# 2_RX_Control.net
KiCad netlist of a schematic drawn in Altium Designer
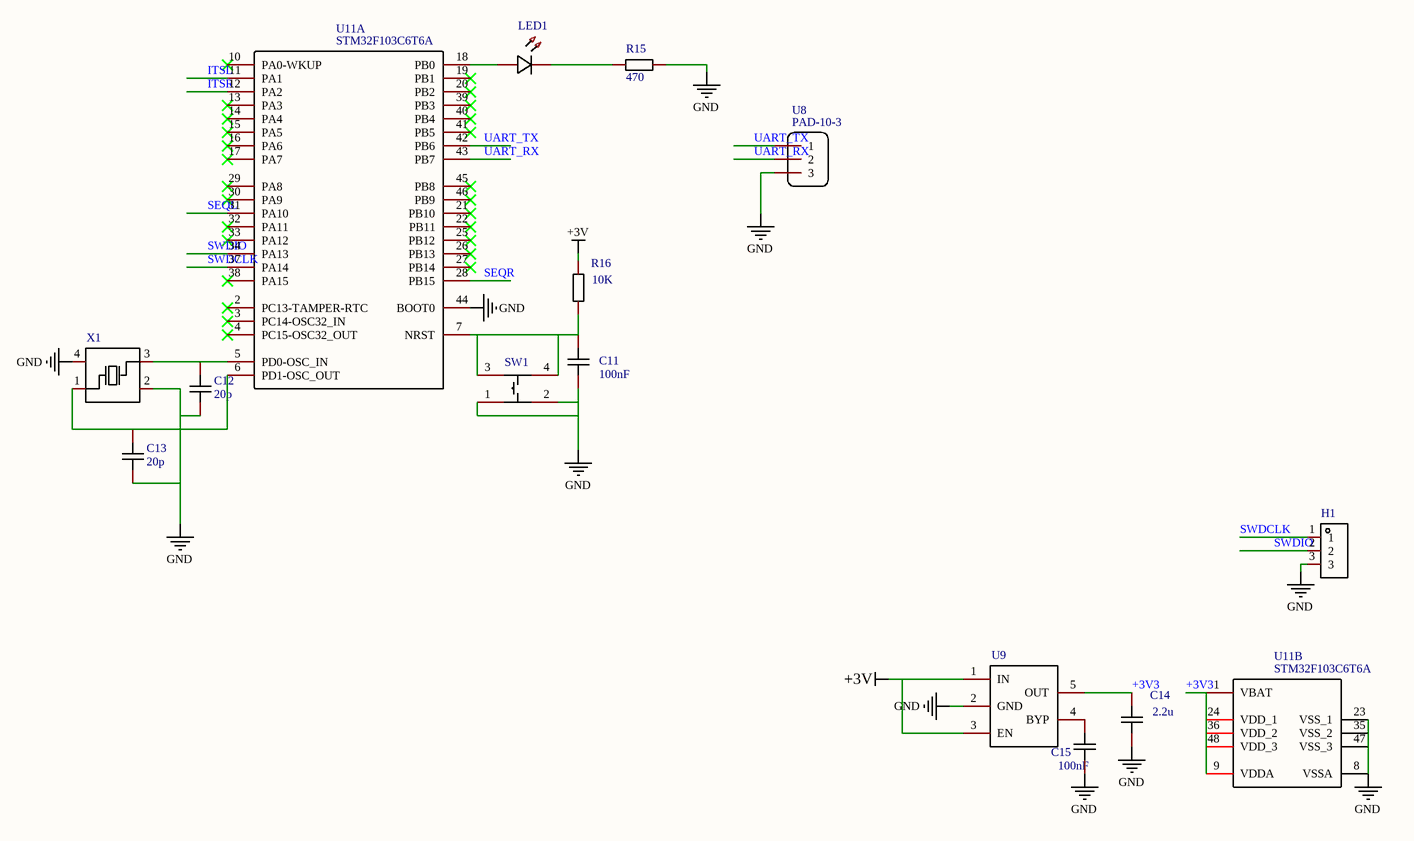
[diagram p0: 2_RX_Control.schdoc]

(export (version "E")
  (design (tool "Eeschema 10.0.6"))
  (components
    (comp (ref "C11")
      (value "100nF")
      (description "容值:100nF;精度:±10%;额定电压:50V;温度系数:X7R;")
      (fields (field (name "Comment") "CAP_0603"))
      (libsource (lib "altium-import") (part "root_1_CAP_0603_"))
    )
    (comp (ref "C12")
      (value "CAP_0603")
      (description "容值:100nF;精度:±10%;额定电压:50V;温度系数:X7R;")
      (fields (field (name "NAME") "20p"))
      (libsource (lib "altium-import") (part "root_1_CAP_0603_"))
    )
    (comp (ref "C13")
      (value "CAP_0603")
      (description "容值:100nF;精度:±10%;额定电压:50V;温度系数:X7R;")
      (fields (field (name "NAME") "20p"))
      (libsource (lib "altium-import") (part "root_1_CAP_0603_"))
    )
    (comp (ref "C14")
      (value "2.2u")
      (description "容值:100nF;精度:±10%;额定电压:50V;温度系数:X7R;")
      (fields (field (name "Comment") "CAP_0603"))
      (libsource (lib "altium-import") (part "root_1_CAP_0603_"))
    )
    (comp (ref "C15")
      (value "100nF")
      (description "容值:100nF;精度:±10%;额定电压:50V;温度系数:X7R;")
      (fields (field (name "Comment") "CAP_0603"))
      (libsource (lib "altium-import") (part "root_1_CAP_0603_"))
    )
    (comp (ref "H1")
      (value "2.54-1*3P正弯针")
      (fields (field (name "MANUFACTURER") "BOOMELE(博穆精密)"))
      (libsource (lib "altium-import") (part "root_0_2.54-1*3P正弯针_"))
    )
    (comp (ref "LED1")
      (value "LED_0603-G")
      (description "照明颜色:翠绿;色温 - CCT（K）:-;主波长/色坐标:520~535nm;")
      (libsource (lib "altium-import") (part "root_0_LED_0603-G_"))
    )
    (comp (ref "R15")
      (value "470")
      (fields (field (name "Comment") "Res_0603"))
      (libsource (lib "altium-import") (part "root_0_Res_0603_"))
    )
    (comp (ref "R16")
      (value "10K")
      (fields (field (name "Comment") "Res_0603"))
      (libsource (lib "altium-import") (part "root_1_Res_0603_"))
    )
    (comp (ref "SW1")
      (value "K2-1809SN-A4DW-06")
      (fields (field (name "MANUFACTURER") "韩国韩荣"))
      (libsource (lib "altium-import") (part "root_0_K2-1809SN-A4DW-06_"))
    )
    (comp (ref "U8")
      (value "PAD-10-3")
      (fields (field (name "NAME") "PAD-10-3"))
      (libsource (lib "altium-import") (part "root_0_PAD-10-3_"))
    )
    (comp (ref "U9")
      (value "MIC5205-3.3YM5-TR")
      (fields (field (name "MANUFACTURER") "MICROCHIP(美国微芯)"))
      (libsource (lib "altium-import") (part "root_0_MIC5205-3.3YM5-TR_"))
    )
    (comp (ref "U11")
      (value "STM32F103C6T6A")
      (fields (field (name "NAME") "STM32F103C6T6A") (field (name "MANUFACTURER") "ST"))
      (libsource (lib "altium-import") (part "root_0_STM32F103C6T6A_"))
    )
    (comp (ref "X1")
      (value "TAXM8M4QLDCDT2T")
      (description "晶振类型:-;频率:-;频率公差:-;频率稳定度:-;负载电容:-;工作温度:-;")
      (fields (field (name "MANUFACTURER") "TAE(雅晶鑫)"))
      (libsource (lib "altium-import") (part "root_0_TAXM8M4QLDCDT2T_"))
    )
  )
  (nets
    (net (code "1") (name "+3V") (class "Default")
      (node (ref "R16") (pin "2") (pinfunction "2_2") (pintype "passive"))
      (node (ref "U9") (pin "1") (pinfunction "IN_1") (pintype "passive"))
      (node (ref "U9") (pin "3") (pinfunction "EN_3") (pintype "passive"))
    )
    (net (code "2") (name "/+3V3") (class "Default")
      (node (ref "C14") (pin "2") (pinfunction "2_2") (pintype "passive"))
      (node (ref "U11") (pin "1") (pinfunction "VBAT_1") (pintype "passive"))
      (node (ref "U11") (pin "24") (pinfunction "VDD_1_24") (pintype "passive"))
      (node (ref "U11") (pin "36") (pinfunction "VDD_2_36") (pintype "passive"))
      (node (ref "U11") (pin "48") (pinfunction "VDD_3_48") (pintype "passive"))
      (node (ref "U11") (pin "9") (pinfunction "VDDA_9") (pintype "passive"))
      (node (ref "U9") (pin "5") (pinfunction "OUT_5") (pintype "passive"))
    )
    (net (code "3") (name "/ITSL") (class "Default")
      (node (ref "U11") (pin "11") (pinfunction "PA1_11") (pintype "passive"))
    )
    (net (code "4") (name "/ITSR") (class "Default")
      (node (ref "U11") (pin "12") (pinfunction "PA2_12") (pintype "passive"))
    )
    (net (code "5") (name "/SEQL") (class "Default")
      (node (ref "U11") (pin "31") (pinfunction "PA10_31") (pintype "passive"))
    )
    (net (code "6") (name "/SEQR") (class "Default")
      (node (ref "U11") (pin "28") (pinfunction "PB15_28") (pintype "passive"))
    )
    (net (code "7") (name "/SWDCLK") (class "Default")
      (node (ref "H1") (pin "1") (pinfunction "1_1") (pintype "passive"))
      (node (ref "U11") (pin "37") (pinfunction "PA14_37") (pintype "passive"))
    )
    (net (code "8") (name "/SWDIO") (class "Default")
      (node (ref "H1") (pin "2") (pinfunction "2_2") (pintype "passive"))
      (node (ref "U11") (pin "34") (pinfunction "PA13_34") (pintype "passive"))
    )
    (net (code "9") (name "/UART_RX") (class "Default")
      (node (ref "U11") (pin "43") (pinfunction "PB7_43") (pintype "passive"))
      (node (ref "U8") (pin "2") (pinfunction "2_2") (pintype "passive"))
    )
    (net (code "10") (name "/UART_TX") (class "Default")
      (node (ref "U11") (pin "42") (pinfunction "PB6_42") (pintype "passive"))
      (node (ref "U8") (pin "1") (pinfunction "1_1") (pintype "passive"))
    )
    (net (code "11") (name "GND") (class "Default")
      (node (ref "C11") (pin "1") (pinfunction "1_1") (pintype "passive"))
      (node (ref "C12") (pin "1") (pinfunction "1_1") (pintype "passive"))
      (node (ref "C13") (pin "1") (pinfunction "1_1") (pintype "passive"))
      (node (ref "C14") (pin "1") (pinfunction "1_1") (pintype "passive"))
      (node (ref "C15") (pin "1") (pinfunction "1_1") (pintype "passive"))
      (node (ref "H1") (pin "3") (pinfunction "3_3") (pintype "passive"))
      (node (ref "R15") (pin "2") (pinfunction "2_2") (pintype "passive"))
      (node (ref "SW1") (pin "1") (pinfunction "1_1") (pintype "passive"))
      (node (ref "SW1") (pin "2") (pinfunction "2_2") (pintype "passive"))
      (node (ref "U11") (pin "23") (pinfunction "VSS_1_23") (pintype "passive"))
      (node (ref "U11") (pin "35") (pinfunction "VSS_2_35") (pintype "passive"))
      (node (ref "U11") (pin "44") (pinfunction "BOOT0_44") (pintype "passive"))
      (node (ref "U11") (pin "47") (pinfunction "VSS_3_47") (pintype "passive"))
      (node (ref "U11") (pin "8") (pinfunction "VSSA_8") (pintype "passive"))
      (node (ref "U8") (pin "3") (pinfunction "3_3") (pintype "passive"))
      (node (ref "U9") (pin "2") (pinfunction "GND_2") (pintype "passive"))
      (node (ref "X1") (pin "2") (pinfunction "GND_2") (pintype "passive"))
      (node (ref "X1") (pin "4") (pinfunction "GND_4") (pintype "passive"))
    )
    (net (code "12") (name "Net-(LED1-A)") (class "Default")
      (node (ref "LED1") (pin "2") (pinfunction "A_2") (pintype "passive"))
      (node (ref "U11") (pin "18") (pinfunction "PB0_18") (pintype "passive"))
    )
    (net (code "13") (name "Net-(LED1-C)") (class "Default")
      (node (ref "LED1") (pin "1") (pinfunction "C_1") (pintype "passive"))
      (node (ref "R15") (pin "1") (pinfunction "1_1") (pintype "passive"))
    )
    (net (code "14") (name "Net-(U9-BYP)") (class "Default")
      (node (ref "C15") (pin "2") (pinfunction "2_2") (pintype "passive"))
      (node (ref "U9") (pin "4") (pinfunction "BYP_4") (pintype "passive"))
    )
    (net (code "15") (name "Net-(U11A-NRST)") (class "Default")
      (node (ref "C11") (pin "2") (pinfunction "2_2") (pintype "passive"))
      (node (ref "R16") (pin "1") (pinfunction "1_1") (pintype "passive"))
      (node (ref "SW1") (pin "3") (pinfunction "3_3") (pintype "passive"))
      (node (ref "SW1") (pin "4") (pinfunction "4_4") (pintype "passive"))
      (node (ref "U11") (pin "7") (pinfunction "NRST_7") (pintype "passive"))
    )
    (net (code "16") (name "Net-(U11A-PD0-OSC_IN)") (class "Default")
      (node (ref "C12") (pin "2") (pinfunction "2_2") (pintype "passive"))
      (node (ref "U11") (pin "5") (pinfunction "PD0-OSC_IN_5") (pintype "passive"))
      (node (ref "X1") (pin "3") (pinfunction "OSC2_3") (pintype "passive"))
    )
    (net (code "17") (name "Net-(U11A-PD1-OSC_OUT)") (class "Default")
      (node (ref "C13") (pin "2") (pinfunction "2_2") (pintype "passive"))
      (node (ref "U11") (pin "6") (pinfunction "PD1-OSC_OUT_6") (pintype "passive"))
      (node (ref "X1") (pin "1") (pinfunction "OSC1_1") (pintype "passive"))
    )
    (net (code "18") (name "unconnected-(U11A-PA0-WKUP-Pad10)") (class "Default")
      (node (ref "U11") (pin "10") (pinfunction "PA0-WKUP_10") (pintype "passive+no_connect"))
    )
    (net (code "19") (name "unconnected-(U11A-PA3-Pad13)") (class "Default")
      (node (ref "U11") (pin "13") (pinfunction "PA3_13") (pintype "passive+no_connect"))
    )
    (net (code "20") (name "unconnected-(U11A-PA4-Pad14)") (class "Default")
      (node (ref "U11") (pin "14") (pinfunction "PA4_14") (pintype "passive+no_connect"))
    )
    (net (code "21") (name "unconnected-(U11A-PA5-Pad15)") (class "Default")
      (node (ref "U11") (pin "15") (pinfunction "PA5_15") (pintype "passive+no_connect"))
    )
    (net (code "22") (name "unconnected-(U11A-PA6-Pad16)") (class "Default")
      (node (ref "U11") (pin "16") (pinfunction "PA6_16") (pintype "passive+no_connect"))
    )
    (net (code "23") (name "unconnected-(U11A-PA7-Pad17)") (class "Default")
      (node (ref "U11") (pin "17") (pinfunction "PA7_17") (pintype "passive+no_connect"))
    )
    (net (code "24") (name "unconnected-(U11A-PA8-Pad29)") (class "Default")
      (node (ref "U11") (pin "29") (pinfunction "PA8_29") (pintype "passive+no_connect"))
    )
    (net (code "25") (name "unconnected-(U11A-PA9-Pad30)") (class "Default")
      (node (ref "U11") (pin "30") (pinfunction "PA9_30") (pintype "passive+no_connect"))
    )
    (net (code "26") (name "unconnected-(U11A-PA11-Pad32)") (class "Default")
      (node (ref "U11") (pin "32") (pinfunction "PA11_32") (pintype "passive+no_connect"))
    )
    (net (code "27") (name "unconnected-(U11A-PA12-Pad33)") (class "Default")
      (node (ref "U11") (pin "33") (pinfunction "PA12_33") (pintype "passive+no_connect"))
    )
    (net (code "28") (name "unconnected-(U11A-PA15-Pad38)") (class "Default")
      (node (ref "U11") (pin "38") (pinfunction "PA15_38") (pintype "passive+no_connect"))
    )
    (net (code "29") (name "unconnected-(U11A-PB1-Pad19)") (class "Default")
      (node (ref "U11") (pin "19") (pinfunction "PB1_19") (pintype "passive+no_connect"))
    )
    (net (code "30") (name "unconnected-(U11A-PB2-Pad20)") (class "Default")
      (node (ref "U11") (pin "20") (pinfunction "PB2_20") (pintype "passive+no_connect"))
    )
    (net (code "31") (name "unconnected-(U11A-PB3-Pad39)") (class "Default")
      (node (ref "U11") (pin "39") (pinfunction "PB3_39") (pintype "passive+no_connect"))
    )
    (net (code "32") (name "unconnected-(U11A-PB4-Pad40)") (class "Default")
      (node (ref "U11") (pin "40") (pinfunction "PB4_40") (pintype "passive+no_connect"))
    )
    (net (code "33") (name "unconnected-(U11A-PB5-Pad41)") (class "Default")
      (node (ref "U11") (pin "41") (pinfunction "PB5_41") (pintype "passive+no_connect"))
    )
    (net (code "34") (name "unconnected-(U11A-PB8-Pad45)") (class "Default")
      (node (ref "U11") (pin "45") (pinfunction "PB8_45") (pintype "passive+no_connect"))
    )
    (net (code "35") (name "unconnected-(U11A-PB9-Pad46)") (class "Default")
      (node (ref "U11") (pin "46") (pinfunction "PB9_46") (pintype "passive+no_connect"))
    )
    (net (code "36") (name "unconnected-(U11A-PB10-Pad21)") (class "Default")
      (node (ref "U11") (pin "21") (pinfunction "PB10_21") (pintype "passive+no_connect"))
    )
    (net (code "37") (name "unconnected-(U11A-PB11-Pad22)") (class "Default")
      (node (ref "U11") (pin "22") (pinfunction "PB11_22") (pintype "passive+no_connect"))
    )
    (net (code "38") (name "unconnected-(U11A-PB12-Pad25)") (class "Default")
      (node (ref "U11") (pin "25") (pinfunction "PB12_25") (pintype "passive+no_connect"))
    )
    (net (code "39") (name "unconnected-(U11A-PB13-Pad26)") (class "Default")
      (node (ref "U11") (pin "26") (pinfunction "PB13_26") (pintype "passive+no_connect"))
    )
    (net (code "40") (name "unconnected-(U11A-PB14-Pad27)") (class "Default")
      (node (ref "U11") (pin "27") (pinfunction "PB14_27") (pintype "passive+no_connect"))
    )
    (net (code "41") (name "unconnected-(U11A-PC13-TAMPER-RTC-Pad2)") (class "Default")
      (node (ref "U11") (pin "2") (pinfunction "PC13-TAMPER-RTC_2") (pintype "passive+no_connect"))
    )
    (net (code "42") (name "unconnected-(U11A-PC14-OSC32_IN-Pad3)") (class "Default")
      (node (ref "U11") (pin "3") (pinfunction "PC14-OSC32_IN_3") (pintype "passive+no_connect"))
    )
    (net (code "43") (name "unconnected-(U11A-PC15-OSC32_OUT-Pad4)") (class "Default")
      (node (ref "U11") (pin "4") (pinfunction "PC15-OSC32_OUT_4") (pintype "passive+no_connect"))
    )
  )
)
